# soraduino.net
KiCad netlist of a schematic drawn in EAGLE
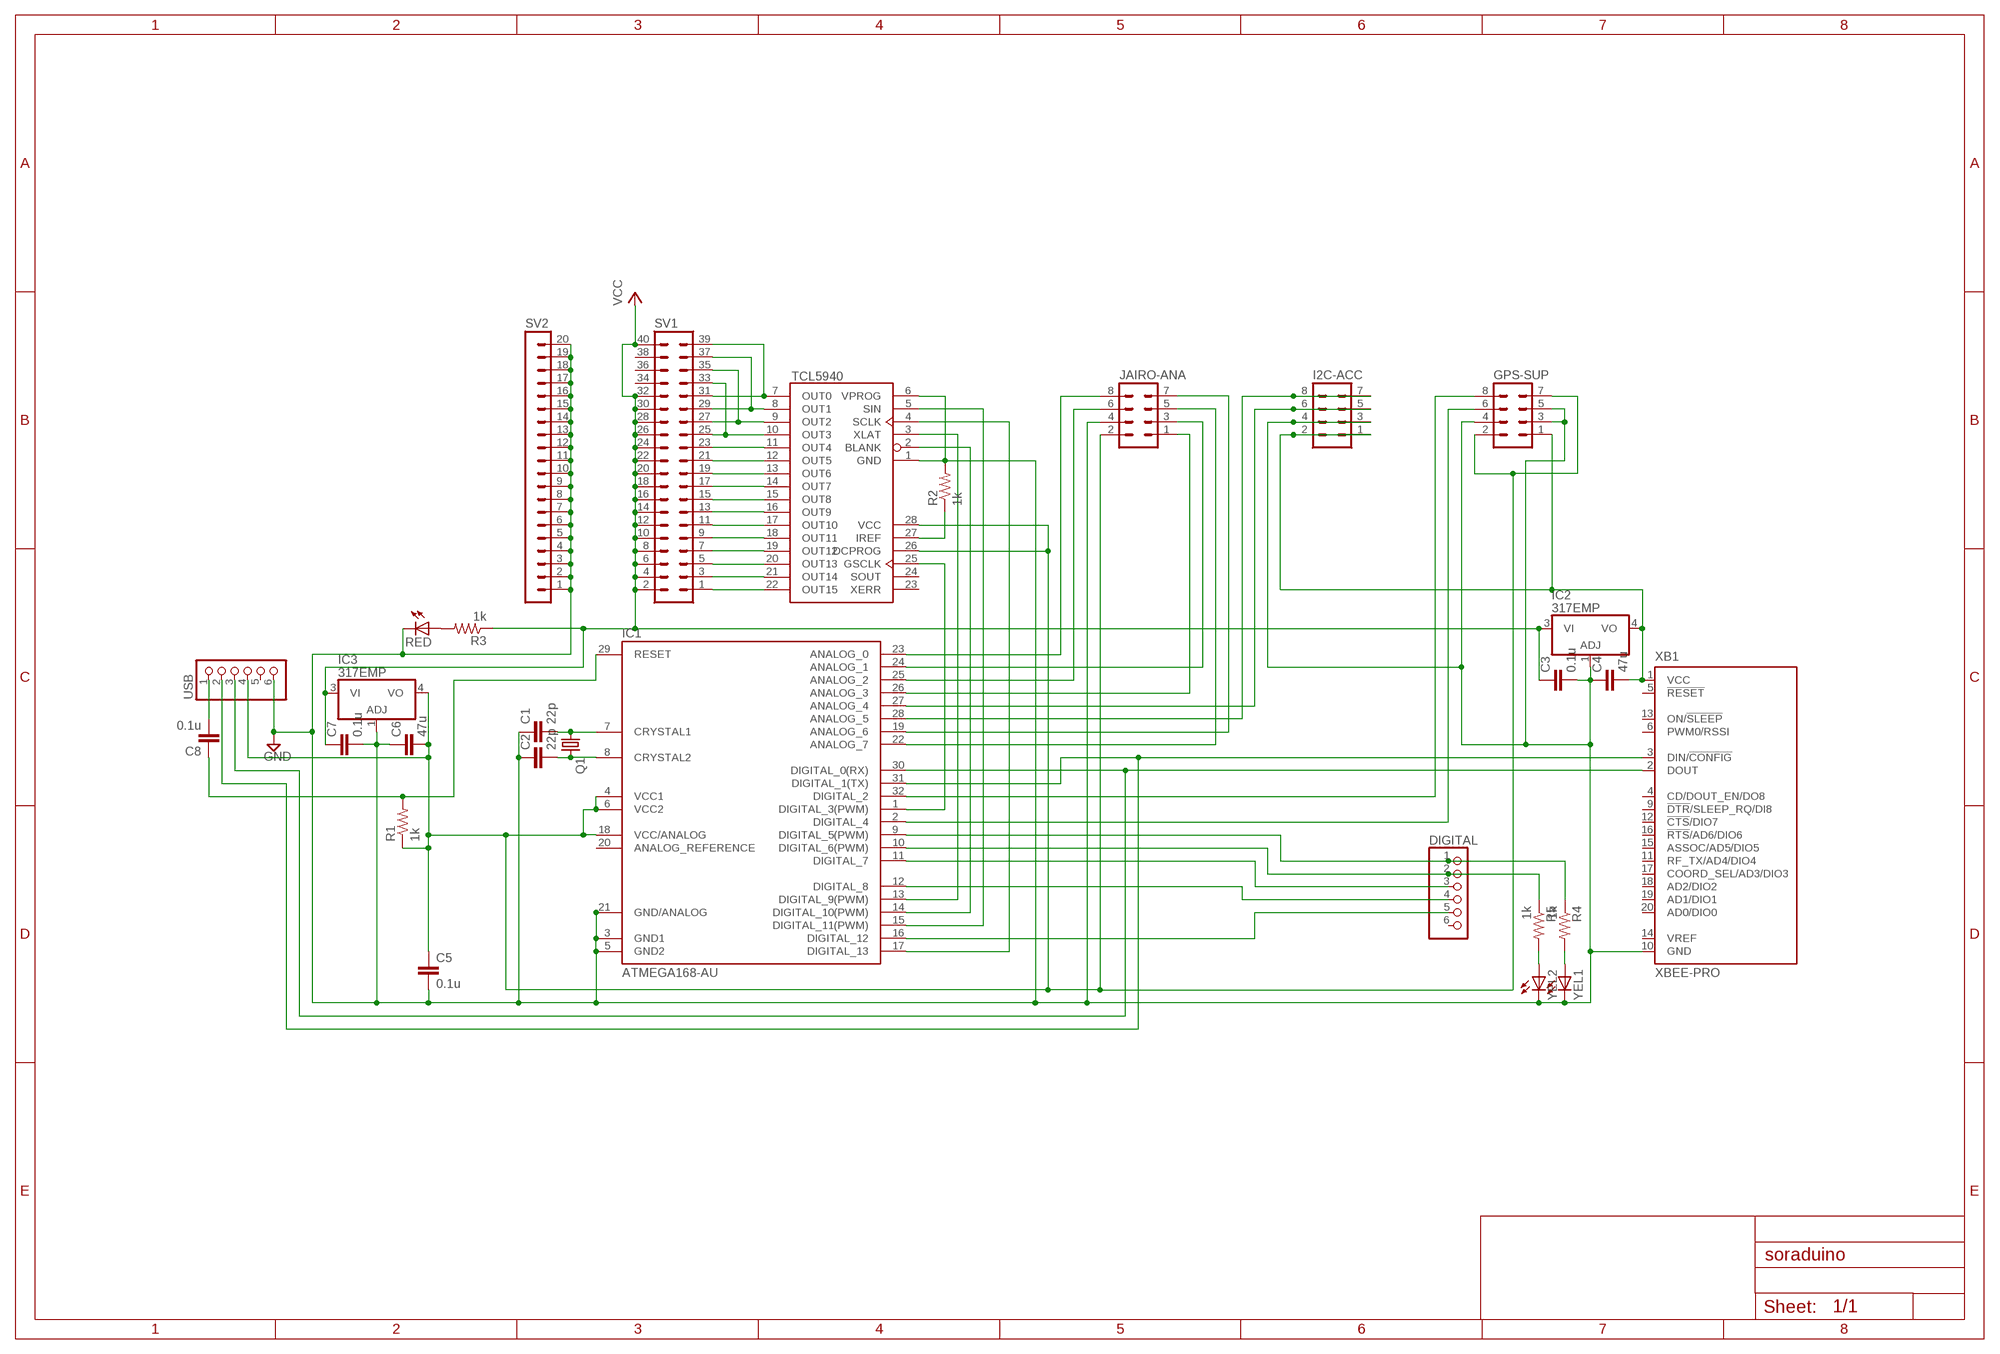
[diagram p0: schematic, sheet 1]

(export (version "E")
  (design (tool "Eeschema 10.0.6"))
  (components
    (comp (ref "C1")
      (value "22p")
      (footprint "eagle-import:C050-024X044")
      (libsource (lib "eagle-import") (part "C-EU050-024X044"))
    )
    (comp (ref "C2")
      (value "22p")
      (footprint "eagle-import:C050-024X044")
      (libsource (lib "eagle-import") (part "C-EU050-024X044"))
    )
    (comp (ref "C3")
      (value "0.1u")
      (footprint "eagle-import:C0805K")
      (libsource (lib "eagle-import") (part "resistor_C-EUC0805K"))
    )
    (comp (ref "C4")
      (value "47u")
      (footprint "eagle-import:C0805K")
      (libsource (lib "eagle-import") (part "resistor_C-EUC0805K"))
    )
    (comp (ref "C5")
      (value "0.1u")
      (footprint "eagle-import:C0805K")
      (libsource (lib "eagle-import") (part "resistor_C-EUC0805K"))
    )
    (comp (ref "C6")
      (value "47u")
      (footprint "eagle-import:C0805K")
      (libsource (lib "eagle-import") (part "resistor_C-EUC0805K"))
    )
    (comp (ref "C7")
      (value "0.1u")
      (footprint "eagle-import:C0805K")
      (libsource (lib "eagle-import") (part "resistor_C-EUC0805K"))
    )
    (comp (ref "C8")
      (value "0.1u")
      (footprint "eagle-import:C0805K")
      (libsource (lib "eagle-import") (part "resistor_C-EUC0805K"))
    )
    (comp (ref "DIGITAL")
      (value "PINHD-1X6")
      (footprint "eagle-import:1X06")
      (libsource (lib "eagle-import") (part "PINHD-1X6"))
    )
    (comp (ref "GPS-SUP")
      (value "MA04-2")
      (footprint "eagle-import:MA04-2")
      (libsource (lib "eagle-import") (part "MA04-2"))
    )
    (comp (ref "I2C-ACC")
      (value "MA04-2")
      (footprint "eagle-import:MA04-2")
      (libsource (lib "eagle-import") (part "MA04-2"))
    )
    (comp (ref "IC1")
      (value "ATMEGA168-AU")
      (footprint "eagle-import:TQFP32-08")
      (libsource (lib "eagle-import") (part "ATMEGA168-AU"))
    )
    (comp (ref "IC2")
      (value "317EMP")
      (footprint "eagle-import:SOT223")
      (libsource (lib "eagle-import") (part "317EMP"))
    )
    (comp (ref "IC3")
      (value "317EMP")
      (footprint "eagle-import:SOT223")
      (libsource (lib "eagle-import") (part "317EMP"))
    )
    (comp (ref "IC4")
      (value "TCL5940SOP")
      (footprint "eagle-import:HTSSOP28PIN")
      (libsource (lib "eagle-import") (part "TCL5940SOP"))
    )
    (comp (ref "JAIRO-ANA")
      (value "MA04-2")
      (footprint "eagle-import:MA04-2")
      (libsource (lib "eagle-import") (part "MA04-2"))
    )
    (comp (ref "Q1")
      (value "CRYSTALHC49S")
      (footprint "eagle-import:HC49_S")
      (libsource (lib "eagle-import") (part "CRYSTALHC49S"))
    )
    (comp (ref "R1")
      (value "1k")
      (footprint "eagle-import:R0603")
      (libsource (lib "eagle-import") (part "R-US_R0603"))
    )
    (comp (ref "R2")
      (value "1k")
      (footprint "eagle-import:R0603")
      (libsource (lib "eagle-import") (part "R-US_R0603"))
    )
    (comp (ref "R3")
      (value "1k")
      (footprint "eagle-import:R0603")
      (libsource (lib "eagle-import") (part "R-US_R0603"))
    )
    (comp (ref "R4")
      (value "1k")
      (footprint "eagle-import:R0603")
      (libsource (lib "eagle-import") (part "R-US_R0603"))
    )
    (comp (ref "R5")
      (value "1k")
      (footprint "eagle-import:R0603")
      (libsource (lib "eagle-import") (part "R-US_R0603"))
    )
    (comp (ref "RED")
      (value "LEDCHIPLED_1206")
      (footprint "eagle-import:CHIPLED_1206")
      (libsource (lib "eagle-import") (part "LEDCHIPLED_1206"))
    )
    (comp (ref "SV1")
      (value "MA20-2")
      (footprint "eagle-import:MA20-2")
      (libsource (lib "eagle-import") (part "MA20-2"))
    )
    (comp (ref "SV2")
      (value "MA20-1")
      (footprint "eagle-import:MA20-1")
      (libsource (lib "eagle-import") (part "MA20-1"))
    )
    (comp (ref "USB")
      (value "PINHD-1X6")
      (footprint "eagle-import:1X06")
      (libsource (lib "eagle-import") (part "PINHD-1X6"))
    )
    (comp (ref "XB1")
      (value "XBEE-PRO")
      (footprint "eagle-import:XBEE-PRO")
      (fields (field (name "MPN") "XBP24-AWI-001"))
      (libsource (lib "eagle-import") (part "XBEE-PRO"))
    )
    (comp (ref "YEL1")
      (value "LEDCHIPLED_1206")
      (footprint "eagle-import:CHIPLED_1206")
      (libsource (lib "eagle-import") (part "LEDCHIPLED_1206"))
    )
    (comp (ref "YEL2")
      (value "LEDCHIPLED_1206")
      (footprint "eagle-import:CHIPLED_1206")
      (libsource (lib "eagle-import") (part "LEDCHIPLED_1206"))
    )
  )
  (nets
    (net (code "1") (name "GND") (class "Default")
      (node (ref "C1") (pin "1") (pinfunction "1_1") (pintype "passive"))
      (node (ref "C2") (pin "1") (pinfunction "1_1") (pintype "passive"))
      (node (ref "C3") (pin "2") (pinfunction "2_2") (pintype "passive"))
      (node (ref "C4") (pin "1") (pinfunction "1_1") (pintype "passive"))
      (node (ref "C5") (pin "2") (pinfunction "2_2") (pintype "passive"))
      (node (ref "C6") (pin "1") (pinfunction "1_1") (pintype "passive"))
      (node (ref "C7") (pin "2") (pinfunction "2_2") (pintype "passive"))
      (node (ref "GPS-SUP") (pin "3") (pinfunction "3_3") (pintype "passive"))
      (node (ref "GPS-SUP") (pin "4") (pinfunction "4_4") (pintype "passive"))
      (node (ref "GPS-SUP") (pin "5") (pinfunction "5_5") (pintype "passive"))
      (node (ref "I2C-ACC") (pin "3") (pinfunction "3_3") (pintype "passive"))
      (node (ref "I2C-ACC") (pin "4") (pinfunction "4_4") (pintype "passive"))
      (node (ref "IC1") (pin "21") (pinfunction "GND/ANALOG_21") (pintype "power_in"))
      (node (ref "IC1") (pin "3") (pinfunction "GND1_3") (pintype "power_in"))
      (node (ref "IC1") (pin "5") (pinfunction "GND2_5") (pintype "power_in"))
      (node (ref "IC2") (pin "1") (pinfunction "ADJ_1") (pintype "input"))
      (node (ref "IC3") (pin "1") (pinfunction "ADJ_1") (pintype "input"))
      (node (ref "IC4") (pin "1") (pinfunction "GND_1") (pintype "power_in"))
      (node (ref "IC4") (pin "6") (pinfunction "VPROG_6") (pintype "bidirectional"))
      (node (ref "JAIRO-ANA") (pin "4") (pinfunction "4_4") (pintype "passive"))
      (node (ref "R2") (pin "2") (pinfunction "2_2") (pintype "passive"))
      (node (ref "RED") (pin "C") (pinfunction "C_C") (pintype "passive"))
      (node (ref "SV2") (pin "1") (pinfunction "1_1") (pintype "passive"))
      (node (ref "SV2") (pin "10") (pinfunction "10_10") (pintype "passive"))
      (node (ref "SV2") (pin "11") (pinfunction "11_11") (pintype "passive"))
      (node (ref "SV2") (pin "12") (pinfunction "12_12") (pintype "passive"))
      (node (ref "SV2") (pin "13") (pinfunction "13_13") (pintype "passive"))
      (node (ref "SV2") (pin "14") (pinfunction "14_14") (pintype "passive"))
      (node (ref "SV2") (pin "15") (pinfunction "15_15") (pintype "passive"))
      (node (ref "SV2") (pin "16") (pinfunction "16_16") (pintype "passive"))
      (node (ref "SV2") (pin "17") (pinfunction "17_17") (pintype "passive"))
      (node (ref "SV2") (pin "18") (pinfunction "18_18") (pintype "passive"))
      (node (ref "SV2") (pin "19") (pinfunction "19_19") (pintype "passive"))
      (node (ref "SV2") (pin "2") (pinfunction "2_2") (pintype "passive"))
      (node (ref "SV2") (pin "20") (pinfunction "20_20") (pintype "passive"))
      (node (ref "SV2") (pin "3") (pinfunction "3_3") (pintype "passive"))
      (node (ref "SV2") (pin "4") (pinfunction "4_4") (pintype "passive"))
      (node (ref "SV2") (pin "5") (pinfunction "5_5") (pintype "passive"))
      (node (ref "SV2") (pin "6") (pinfunction "6_6") (pintype "passive"))
      (node (ref "SV2") (pin "7") (pinfunction "7_7") (pintype "passive"))
      (node (ref "SV2") (pin "8") (pinfunction "8_8") (pintype "passive"))
      (node (ref "SV2") (pin "9") (pinfunction "9_9") (pintype "passive"))
      (node (ref "USB") (pin "6") (pinfunction "6_6") (pintype "passive"))
      (node (ref "XB1") (pin "10") (pinfunction "GND_10") (pintype "power_in"))
      (node (ref "YEL1") (pin "C") (pinfunction "C_C") (pintype "passive"))
      (node (ref "YEL2") (pin "C") (pinfunction "C_C") (pintype "passive"))
    )
    (net (code "2") (name "Net-(C8-Pad2)") (class "Default")
      (node (ref "C8") (pin "2") (pinfunction "2_2") (pintype "passive"))
      (node (ref "USB") (pin "1") (pinfunction "1_1") (pintype "passive"))
    )
    (net (code "3") (name "Net-(IC1-ANALOG_0)") (class "Default")
      (node (ref "IC1") (pin "23") (pinfunction "ANALOG_0_23") (pintype "bidirectional"))
      (node (ref "JAIRO-ANA") (pin "8") (pinfunction "8_8") (pintype "passive"))
    )
    (net (code "4") (name "Net-(IC1-ANALOG_1)") (class "Default")
      (node (ref "IC1") (pin "24") (pinfunction "ANALOG_1_24") (pintype "bidirectional"))
      (node (ref "JAIRO-ANA") (pin "3") (pinfunction "3_3") (pintype "passive"))
    )
    (net (code "5") (name "Net-(IC1-ANALOG_2)") (class "Default")
      (node (ref "IC1") (pin "25") (pinfunction "ANALOG_2_25") (pintype "bidirectional"))
      (node (ref "JAIRO-ANA") (pin "6") (pinfunction "6_6") (pintype "passive"))
    )
    (net (code "6") (name "Net-(IC1-ANALOG_3)") (class "Default")
      (node (ref "IC1") (pin "26") (pinfunction "ANALOG_3_26") (pintype "bidirectional"))
      (node (ref "JAIRO-ANA") (pin "1") (pinfunction "1_1") (pintype "passive"))
    )
    (net (code "7") (name "Net-(IC1-ANALOG_4)") (class "Default")
      (node (ref "I2C-ACC") (pin "5") (pinfunction "5_5") (pintype "passive"))
      (node (ref "I2C-ACC") (pin "6") (pinfunction "6_6") (pintype "passive"))
      (node (ref "IC1") (pin "27") (pinfunction "ANALOG_4_27") (pintype "bidirectional"))
    )
    (net (code "8") (name "Net-(IC1-ANALOG_5)") (class "Default")
      (node (ref "I2C-ACC") (pin "7") (pinfunction "7_7") (pintype "passive"))
      (node (ref "I2C-ACC") (pin "8") (pinfunction "8_8") (pintype "passive"))
      (node (ref "IC1") (pin "28") (pinfunction "ANALOG_5_28") (pintype "bidirectional"))
    )
    (net (code "9") (name "Net-(IC1-ANALOG_6)") (class "Default")
      (node (ref "IC1") (pin "19") (pinfunction "ANALOG_6_19") (pintype "passive"))
      (node (ref "JAIRO-ANA") (pin "7") (pinfunction "7_7") (pintype "passive"))
    )
    (net (code "10") (name "Net-(IC1-ANALOG_7)") (class "Default")
      (node (ref "IC1") (pin "22") (pinfunction "ANALOG_7_22") (pintype "passive"))
      (node (ref "JAIRO-ANA") (pin "5") (pinfunction "5_5") (pintype "passive"))
    )
    (net (code "11") (name "Net-(IC1-CRYSTAL1)") (class "Default")
      (node (ref "C1") (pin "2") (pinfunction "2_2") (pintype "passive"))
      (node (ref "IC1") (pin "7") (pinfunction "CRYSTAL1_7") (pintype "bidirectional"))
      (node (ref "Q1") (pin "1") (pinfunction "1_1") (pintype "passive"))
    )
    (net (code "12") (name "Net-(IC1-CRYSTAL2)") (class "Default")
      (node (ref "C2") (pin "2") (pinfunction "2_2") (pintype "passive"))
      (node (ref "IC1") (pin "8") (pinfunction "CRYSTAL2_8") (pintype "bidirectional"))
      (node (ref "Q1") (pin "2") (pinfunction "2_2") (pintype "passive"))
    )
    (net (code "13") (name "Net-(IC1-DIGITAL_0(RX))") (class "Default")
      (node (ref "IC1") (pin "30") (pinfunction "DIGITAL_0(RX)_30") (pintype "bidirectional"))
      (node (ref "USB") (pin "3") (pinfunction "3_3") (pintype "passive"))
      (node (ref "XB1") (pin "2") (pinfunction "DOUT_2") (pintype "output"))
    )
    (net (code "14") (name "Net-(IC1-DIGITAL_1(TX))") (class "Default")
      (node (ref "IC1") (pin "31") (pinfunction "DIGITAL_1(TX)_31") (pintype "bidirectional"))
      (node (ref "USB") (pin "2") (pinfunction "2_2") (pintype "passive"))
      (node (ref "XB1") (pin "3") (pinfunction "DIN/~{CONFIG}_3") (pintype "input"))
    )
    (net (code "15") (name "Net-(IC1-DIGITAL_2)") (class "Default")
      (node (ref "GPS-SUP") (pin "8") (pinfunction "8_8") (pintype "passive"))
      (node (ref "IC1") (pin "32") (pinfunction "DIGITAL_2_32") (pintype "bidirectional"))
    )
    (net (code "16") (name "Net-(IC1-DIGITAL_3(PWM))") (class "Default")
      (node (ref "IC1") (pin "1") (pinfunction "DIGITAL_3(PWM)_1") (pintype "bidirectional"))
      (node (ref "IC4") (pin "25") (pinfunction "GSCLK_25") (pintype "input"))
    )
    (net (code "17") (name "Net-(IC1-DIGITAL_4)") (class "Default")
      (node (ref "GPS-SUP") (pin "6") (pinfunction "6_6") (pintype "passive"))
      (node (ref "IC1") (pin "2") (pinfunction "DIGITAL_4_2") (pintype "bidirectional"))
    )
    (net (code "18") (name "Net-(IC1-DIGITAL_5(PWM))") (class "Default")
      (node (ref "DIGITAL") (pin "1") (pinfunction "1_1") (pintype "passive"))
      (node (ref "IC1") (pin "9") (pinfunction "DIGITAL_5(PWM)_9") (pintype "bidirectional"))
      (node (ref "R4") (pin "1") (pinfunction "1_1") (pintype "passive"))
    )
    (net (code "19") (name "Net-(IC1-DIGITAL_6(PWM))") (class "Default")
      (node (ref "DIGITAL") (pin "2") (pinfunction "2_2") (pintype "passive"))
      (node (ref "IC1") (pin "10") (pinfunction "DIGITAL_6(PWM)_10") (pintype "bidirectional"))
      (node (ref "R5") (pin "1") (pinfunction "1_1") (pintype "passive"))
    )
    (net (code "20") (name "Net-(IC1-DIGITAL_7)") (class "Default")
      (node (ref "DIGITAL") (pin "3") (pinfunction "3_3") (pintype "passive"))
      (node (ref "IC1") (pin "11") (pinfunction "DIGITAL_7_11") (pintype "bidirectional"))
    )
    (net (code "21") (name "Net-(IC1-DIGITAL_8)") (class "Default")
      (node (ref "DIGITAL") (pin "4") (pinfunction "4_4") (pintype "passive"))
      (node (ref "IC1") (pin "12") (pinfunction "DIGITAL_8_12") (pintype "bidirectional"))
    )
    (net (code "22") (name "Net-(IC1-DIGITAL_9(PWM))") (class "Default")
      (node (ref "IC1") (pin "13") (pinfunction "DIGITAL_9(PWM)_13") (pintype "bidirectional"))
      (node (ref "IC4") (pin "3") (pinfunction "XLAT_3") (pintype "input"))
    )
    (net (code "23") (name "Net-(IC1-DIGITAL_10(PWM))") (class "Default")
      (node (ref "IC1") (pin "14") (pinfunction "DIGITAL_10(PWM)_14") (pintype "bidirectional"))
      (node (ref "IC4") (pin "2") (pinfunction "BLANK_2") (pintype "input"))
    )
    (net (code "24") (name "Net-(IC1-DIGITAL_11(PWM))") (class "Default")
      (node (ref "IC1") (pin "15") (pinfunction "DIGITAL_11(PWM)_15") (pintype "bidirectional"))
      (node (ref "IC4") (pin "5") (pinfunction "SIN_5") (pintype "input"))
    )
    (net (code "25") (name "Net-(IC1-DIGITAL_12)") (class "Default")
      (node (ref "DIGITAL") (pin "5") (pinfunction "5_5") (pintype "passive"))
      (node (ref "IC1") (pin "16") (pinfunction "DIGITAL_12_16") (pintype "bidirectional"))
    )
    (net (code "26") (name "Net-(IC1-DIGITAL_13)") (class "Default")
      (node (ref "IC1") (pin "17") (pinfunction "DIGITAL_13_17") (pintype "bidirectional"))
      (node (ref "IC4") (pin "4") (pinfunction "SCLK_4") (pintype "input"))
    )
    (net (code "27") (name "Net-(IC1-RESET)") (class "Default")
      (node (ref "C8") (pin "1") (pinfunction "1_1") (pintype "passive"))
      (node (ref "IC1") (pin "29") (pinfunction "RESET_29") (pintype "bidirectional"))
      (node (ref "R1") (pin "2") (pinfunction "2_2") (pintype "passive"))
    )
    (net (code "28") (name "Net-(IC1-VCC1)") (class "Default")
      (node (ref "C5") (pin "1") (pinfunction "1_1") (pintype "passive"))
      (node (ref "C6") (pin "2") (pinfunction "2_2") (pintype "passive"))
      (node (ref "GPS-SUP") (pin "2") (pinfunction "2_2") (pintype "passive"))
      (node (ref "GPS-SUP") (pin "7") (pinfunction "7_7") (pintype "passive"))
      (node (ref "IC1") (pin "18") (pinfunction "VCC/ANALOG_18") (pintype "passive"))
      (node (ref "IC1") (pin "4") (pinfunction "VCC1_4") (pintype "power_in"))
      (node (ref "IC1") (pin "6") (pinfunction "VCC2_6") (pintype "power_in"))
      (node (ref "IC3") (pin "4") (pinfunction "VO_4") (pintype "passive"))
      (node (ref "IC4") (pin "26") (pinfunction "DCPROG_26") (pintype "input"))
      (node (ref "IC4") (pin "28") (pinfunction "VCC_28") (pintype "power_in"))
      (node (ref "JAIRO-ANA") (pin "2") (pinfunction "2_2") (pintype "passive"))
      (node (ref "R1") (pin "1") (pinfunction "1_1") (pintype "passive"))
      (node (ref "USB") (pin "4") (pinfunction "4_4") (pintype "passive"))
    )
    (net (code "29") (name "Net-(IC2-VO)") (class "Default")
      (node (ref "C4") (pin "2") (pinfunction "2_2") (pintype "passive"))
      (node (ref "GPS-SUP") (pin "1") (pinfunction "1_1") (pintype "passive"))
      (node (ref "I2C-ACC") (pin "1") (pinfunction "1_1") (pintype "passive"))
      (node (ref "I2C-ACC") (pin "2") (pinfunction "2_2") (pintype "passive"))
      (node (ref "IC2") (pin "4") (pinfunction "VO_4") (pintype "passive"))
      (node (ref "XB1") (pin "1") (pinfunction "VCC_1") (pintype "power_in"))
    )
    (net (code "30") (name "Net-(IC4-IREF)") (class "Default")
      (node (ref "IC4") (pin "27") (pinfunction "IREF_27") (pintype "input"))
      (node (ref "R2") (pin "1") (pinfunction "1_1") (pintype "passive"))
    )
    (net (code "31") (name "Net-(IC4-OUT0)") (class "Default")
      (node (ref "IC4") (pin "7") (pinfunction "OUT0_7") (pintype "output"))
      (node (ref "SV1") (pin "31") (pinfunction "31_31") (pintype "passive"))
      (node (ref "SV1") (pin "39") (pinfunction "39_39") (pintype "passive"))
    )
    (net (code "32") (name "Net-(IC4-OUT1)") (class "Default")
      (node (ref "IC4") (pin "8") (pinfunction "OUT1_8") (pintype "output"))
      (node (ref "SV1") (pin "29") (pinfunction "29_29") (pintype "passive"))
      (node (ref "SV1") (pin "37") (pinfunction "37_37") (pintype "passive"))
    )
    (net (code "33") (name "Net-(IC4-OUT2)") (class "Default")
      (node (ref "IC4") (pin "9") (pinfunction "OUT2_9") (pintype "output"))
      (node (ref "SV1") (pin "27") (pinfunction "27_27") (pintype "passive"))
      (node (ref "SV1") (pin "35") (pinfunction "35_35") (pintype "passive"))
    )
    (net (code "34") (name "Net-(IC4-OUT3)") (class "Default")
      (node (ref "IC4") (pin "10") (pinfunction "OUT3_10") (pintype "output"))
      (node (ref "SV1") (pin "25") (pinfunction "25_25") (pintype "passive"))
      (node (ref "SV1") (pin "33") (pinfunction "33_33") (pintype "passive"))
    )
    (net (code "35") (name "Net-(IC4-OUT4)") (class "Default")
      (node (ref "IC4") (pin "11") (pinfunction "OUT4_11") (pintype "output"))
      (node (ref "SV1") (pin "23") (pinfunction "23_23") (pintype "passive"))
    )
    (net (code "36") (name "Net-(IC4-OUT5)") (class "Default")
      (node (ref "IC4") (pin "12") (pinfunction "OUT5_12") (pintype "output"))
      (node (ref "SV1") (pin "21") (pinfunction "21_21") (pintype "passive"))
    )
    (net (code "37") (name "Net-(IC4-OUT6)") (class "Default")
      (node (ref "IC4") (pin "13") (pinfunction "OUT6_13") (pintype "output"))
      (node (ref "SV1") (pin "19") (pinfunction "19_19") (pintype "passive"))
    )
    (net (code "38") (name "Net-(IC4-OUT7)") (class "Default")
      (node (ref "IC4") (pin "14") (pinfunction "OUT7_14") (pintype "output"))
      (node (ref "SV1") (pin "17") (pinfunction "17_17") (pintype "passive"))
    )
    (net (code "39") (name "Net-(IC4-OUT8)") (class "Default")
      (node (ref "IC4") (pin "15") (pinfunction "OUT8_15") (pintype "output"))
      (node (ref "SV1") (pin "15") (pinfunction "15_15") (pintype "passive"))
    )
    (net (code "40") (name "Net-(IC4-OUT9)") (class "Default")
      (node (ref "IC4") (pin "16") (pinfunction "OUT9_16") (pintype "output"))
      (node (ref "SV1") (pin "13") (pinfunction "13_13") (pintype "passive"))
    )
    (net (code "41") (name "Net-(IC4-OUT10)") (class "Default")
      (node (ref "IC4") (pin "17") (pinfunction "OUT10_17") (pintype "output"))
      (node (ref "SV1") (pin "11") (pinfunction "11_11") (pintype "passive"))
    )
    (net (code "42") (name "Net-(IC4-OUT11)") (class "Default")
      (node (ref "IC4") (pin "18") (pinfunction "OUT11_18") (pintype "output"))
      (node (ref "SV1") (pin "9") (pinfunction "9_9") (pintype "passive"))
    )
    (net (code "43") (name "Net-(IC4-OUT12)") (class "Default")
      (node (ref "IC4") (pin "19") (pinfunction "OUT12_19") (pintype "output"))
      (node (ref "SV1") (pin "7") (pinfunction "7_7") (pintype "passive"))
    )
    (net (code "44") (name "Net-(IC4-OUT13)") (class "Default")
      (node (ref "IC4") (pin "20") (pinfunction "OUT13_20") (pintype "output"))
      (node (ref "SV1") (pin "5") (pinfunction "5_5") (pintype "passive"))
    )
    (net (code "45") (name "Net-(IC4-OUT14)") (class "Default")
      (node (ref "IC4") (pin "21") (pinfunction "OUT14_21") (pintype "output"))
      (node (ref "SV1") (pin "3") (pinfunction "3_3") (pintype "passive"))
    )
    (net (code "46") (name "Net-(IC4-OUT15)") (class "Default")
      (node (ref "IC4") (pin "22") (pinfunction "OUT15_22") (pintype "output"))
      (node (ref "SV1") (pin "1") (pinfunction "1_1") (pintype "passive"))
    )
    (net (code "47") (name "Net-(R3-Pad2)") (class "Default")
      (node (ref "R3") (pin "2") (pinfunction "2_2") (pintype "passive"))
      (node (ref "RED") (pin "A") (pinfunction "A_A") (pintype "passive"))
    )
    (net (code "48") (name "Net-(R4-Pad2)") (class "Default")
      (node (ref "R4") (pin "2") (pinfunction "2_2") (pintype "passive"))
      (node (ref "YEL1") (pin "A") (pinfunction "A_A") (pintype "passive"))
    )
    (net (code "49") (name "Net-(R5-Pad2)") (class "Default")
      (node (ref "R5") (pin "2") (pinfunction "2_2") (pintype "passive"))
      (node (ref "YEL2") (pin "A") (pinfunction "A_A") (pintype "passive"))
    )
    (net (code "50") (name "VCC") (class "Default")
      (node (ref "C3") (pin "1") (pinfunction "1_1") (pintype "passive"))
      (node (ref "C7") (pin "1") (pinfunction "1_1") (pintype "passive"))
      (node (ref "IC2") (pin "3") (pinfunction "VI_3") (pintype "input"))
      (node (ref "IC3") (pin "3") (pinfunction "VI_3") (pintype "input"))
      (node (ref "R3") (pin "1") (pinfunction "1_1") (pintype "passive"))
      (node (ref "SV1") (pin "10") (pinfunction "10_10") (pintype "passive"))
      (node (ref "SV1") (pin "12") (pinfunction "12_12") (pintype "passive"))
      (node (ref "SV1") (pin "14") (pinfunction "14_14") (pintype "passive"))
      (node (ref "SV1") (pin "16") (pinfunction "16_16") (pintype "passive"))
      (node (ref "SV1") (pin "18") (pinfunction "18_18") (pintype "passive"))
      (node (ref "SV1") (pin "2") (pinfunction "2_2") (pintype "passive"))
      (node (ref "SV1") (pin "20") (pinfunction "20_20") (pintype "passive"))
      (node (ref "SV1") (pin "22") (pinfunction "22_22") (pintype "passive"))
      (node (ref "SV1") (pin "24") (pinfunction "24_24") (pintype "passive"))
      (node (ref "SV1") (pin "26") (pinfunction "26_26") (pintype "passive"))
      (node (ref "SV1") (pin "28") (pinfunction "28_28") (pintype "passive"))
      (node (ref "SV1") (pin "30") (pinfunction "30_30") (pintype "passive"))
      (node (ref "SV1") (pin "32") (pinfunction "32_32") (pintype "passive"))
      (node (ref "SV1") (pin "4") (pinfunction "4_4") (pintype "passive"))
      (node (ref "SV1") (pin "40") (pinfunction "40_40") (pintype "passive"))
      (node (ref "SV1") (pin "6") (pinfunction "6_6") (pintype "passive"))
      (node (ref "SV1") (pin "8") (pinfunction "8_8") (pintype "passive"))
    )
    (net (code "51") (name "unconnected-(DIGITAL-Pad6)") (class "Default")
      (node (ref "DIGITAL") (pin "6") (pinfunction "6_6") (pintype "passive"))
    )
    (net (code "52") (name "unconnected-(IC1-ANALOG_REFERENCE-Pad20)") (class "Default")
      (node (ref "IC1") (pin "20") (pinfunction "ANALOG_REFERENCE_20") (pintype "passive"))
    )
    (net (code "53") (name "unconnected-(IC4-SOUT-Pad24)") (class "Default")
      (node (ref "IC4") (pin "24") (pinfunction "SOUT_24") (pintype "output"))
    )
    (net (code "54") (name "unconnected-(IC4-XERR-Pad23)") (class "Default")
      (node (ref "IC4") (pin "23") (pinfunction "XERR_23") (pintype "output"))
    )
    (net (code "55") (name "unconnected-(SV1-Pad34)") (class "Default")
      (node (ref "SV1") (pin "34") (pinfunction "34_34") (pintype "passive"))
    )
    (net (code "56") (name "unconnected-(SV1-Pad36)") (class "Default")
      (node (ref "SV1") (pin "36") (pinfunction "36_36") (pintype "passive"))
    )
    (net (code "57") (name "unconnected-(SV1-Pad38)") (class "Default")
      (node (ref "SV1") (pin "38") (pinfunction "38_38") (pintype "passive"))
    )
    (net (code "58") (name "unconnected-(USB-Pad5)") (class "Default")
      (node (ref "USB") (pin "5") (pinfunction "5_5") (pintype "passive"))
    )
    (net (code "59") (name "unconnected-(XB1-AD0{slash}DIO0-Pad20)") (class "Default")
      (node (ref "XB1") (pin "20") (pinfunction "AD0/DIO0_20") (pintype "bidirectional"))
    )
    (net (code "60") (name "unconnected-(XB1-AD1{slash}DIO1-Pad19)") (class "Default")
      (node (ref "XB1") (pin "19") (pinfunction "AD1/DIO1_19") (pintype "bidirectional"))
    )
    (net (code "61") (name "unconnected-(XB1-AD2{slash}DIO2-Pad18)") (class "Default")
      (node (ref "XB1") (pin "18") (pinfunction "AD2/DIO2_18") (pintype "bidirectional"))
    )
    (net (code "62") (name "unconnected-(XB1-ASSOC{slash}AD5{slash}DIO5-Pad15)") (class "Default")
      (node (ref "XB1") (pin "15") (pinfunction "ASSOC/AD5/DIO5_15") (pintype "bidirectional"))
    )
    (net (code "63") (name "unconnected-(XB1-CD{slash}DOUT_EN{slash}DO8-Pad4)") (class "Default")
      (node (ref "XB1") (pin "4") (pinfunction "CD/DOUT_EN/DO8_4") (pintype "output"))
    )
    (net (code "64") (name "unconnected-(XB1-COORD_SEL{slash}AD3{slash}DIO3-Pad17)") (class "Default")
      (node (ref "XB1") (pin "17") (pinfunction "COORD_SEL/AD3/DIO3_17") (pintype "bidirectional"))
    )
    (net (code "65") (name "unconnected-(XB1-ON{slash}~{SLEEP}-Pad13)") (class "Default")
      (node (ref "XB1") (pin "13") (pinfunction "ON/~{SLEEP}_13") (pintype "output"))
    )
    (net (code "66") (name "unconnected-(XB1-PWM0{slash}RSSI-Pad6)") (class "Default")
      (node (ref "XB1") (pin "6") (pinfunction "PWM0/RSSI_6") (pintype "output"))
    )
    (net (code "67") (name "unconnected-(XB1-RF_TX{slash}AD4{slash}DIO4-Pad11)") (class "Default")
      (node (ref "XB1") (pin "11") (pinfunction "RF_TX/AD4/DIO4_11") (pintype "bidirectional"))
    )
    (net (code "68") (name "unconnected-(XB1-VREF-Pad14)") (class "Default")
      (node (ref "XB1") (pin "14") (pinfunction "VREF_14") (pintype "input"))
    )
    (net (code "69") (name "unconnected-(XB1-~{CTS}{slash}DIO7-Pad12)") (class "Default")
      (node (ref "XB1") (pin "12") (pinfunction "~{CTS}/DIO7_12") (pintype "bidirectional"))
    )
    (net (code "70") (name "unconnected-(XB1-~{DTR}{slash}SLEEP_RQ{slash}DI8-Pad9)") (class "Default")
      (node (ref "XB1") (pin "9") (pinfunction "~{DTR}/SLEEP_RQ/DI8_9") (pintype "bidirectional"))
    )
    (net (code "71") (name "unconnected-(XB1-~{RESET}-Pad5)") (class "Default")
      (node (ref "XB1") (pin "5") (pinfunction "~{RESET}_5") (pintype "input"))
    )
    (net (code "72") (name "unconnected-(XB1-~{RTS}{slash}AD6{slash}DIO6-Pad16)") (class "Default")
      (node (ref "XB1") (pin "16") (pinfunction "~{RTS}/AD6/DIO6_16") (pintype "bidirectional"))
    )
  )
)
